# smd.net
KiCad netlist of a schematic drawn in EAGLE
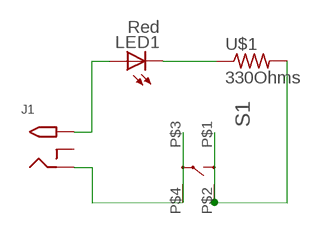
[diagram p0: schematic, sheet 1]

(export (version "E")
  (design (tool "Eeschema 10.0.6"))
  (components
    (comp (ref "J1")
      (value "2.1MMJACKTHM")
      (footprint "eagle-import:PJ-102A")
      (libsource (lib "eagle-import") (part "2.1MMJACKTHM"))
    )
    (comp (ref "LED1")
      (value "Red")
      (footprint "eagle-import:LED5MM")
      (libsource (lib "eagle-import") (part "LED5MM"))
    )
    (comp (ref "S1")
      (value "BUTTON-TACTILE-SQUARE")
      (footprint "eagle-import:BUTTON-TACTILE-SQUARE-LSH")
      (libsource (lib "eagle-import") (part "BUTTON-TACTILE-SQUARE"))
    )
    (comp (ref "U$1")
      (value "330Ohms")
      (footprint "eagle-import:RESAD1160W55L680D260_HS")
      (libsource (lib "eagle-import") (part "RESISTORTH-1/4W-CARBON"))
    )
  )
  (nets
    (net (code "1") (name "Net-(J1-PadTIP)") (class "Default")
      (node (ref "J1") (pin "TIP") (pinfunction "TIP_TIP") (pintype "bidirectional"))
      (node (ref "LED1") (pin "A") (pinfunction "A_A") (pintype "passive"))
    )
    (net (code "2") (name "Net-(LED1-C)") (class "Default")
      (node (ref "LED1") (pin "K") (pinfunction "C_K") (pintype "passive"))
      (node (ref "U$1") (pin "1") (pinfunction "1_1") (pintype "passive"))
    )
    (net (code "3") (name "Net-(S1-P)") (class "Default")
      (node (ref "J1") (pin "RING") (pinfunction "RING_RING") (pintype "bidirectional"))
      (node (ref "S1") (pin "P$3") (pinfunction "P_P$3") (pintype "passive"))
      (node (ref "S1") (pin "P$4") (pinfunction "P1_P$4") (pintype "passive"))
    )
    (net (code "4") (name "Net-(S1-S)") (class "Default")
      (node (ref "S1") (pin "P$1") (pinfunction "S_P$1") (pintype "passive"))
      (node (ref "S1") (pin "P$2") (pinfunction "S1_P$2") (pintype "passive"))
      (node (ref "U$1") (pin "2") (pinfunction "2_2") (pintype "passive"))
    )
    (net (code "5") (name "unconnected-(J1-PadRING_SW)") (class "Default")
      (node (ref "J1") (pin "RING_SW") (pinfunction "RING_SW_RING_SW") (pintype "bidirectional"))
    )
  )
)
